# Schematic_DE1_Project_2021-05-03.net
KiCad netlist of a schematic drawn in Altium Designer
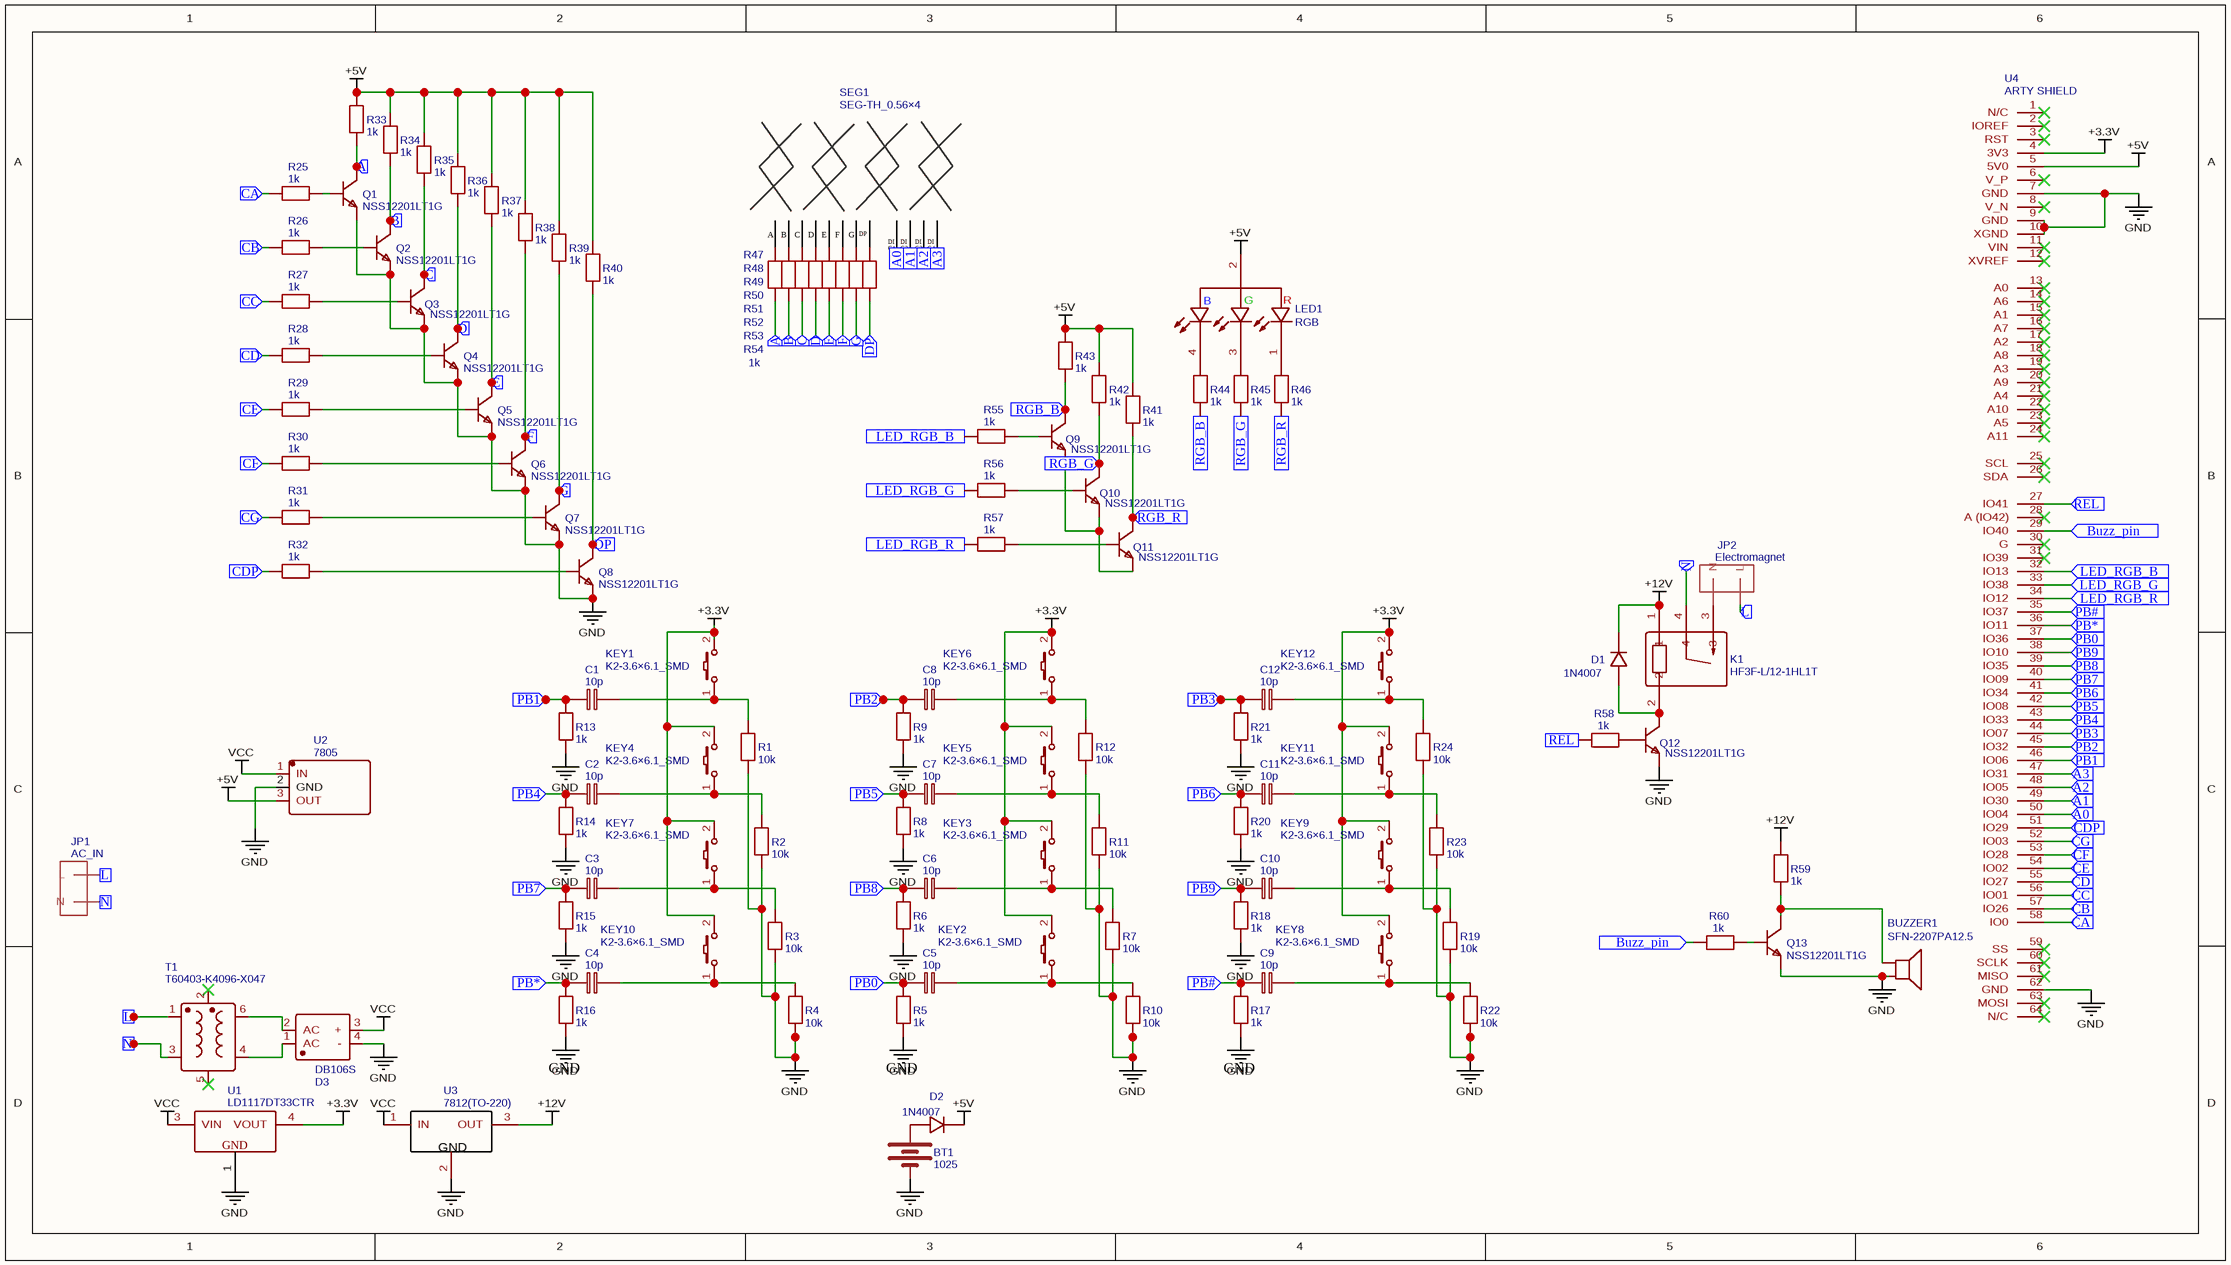
[diagram p0: Schematic_DE1_Project_2021-05-03.schdoc]

(export (version "E")
  (design (tool "Eeschema 10.0.6"))
  (components
    (comp (ref "BT1")
      (value "1025")
      (fields (field (name "BOM_SUPPLIER PART") "C238060") (field (name "CONTRIBUTOR") "LCSC"))
      (libsource (lib "altium-import") (part "root_3_1025_"))
    )
    (comp (ref "BUZZER1")
      (value "SFN-2207PA12.5")
      (fields (field (name "BOM_SUPPLIER PART") "C360602") (field (name "CONTRIBUTOR") "LCSC"))
      (libsource (lib "altium-import") (part "root_0_SFN-2207PA12.5_"))
    )
    (comp (ref "C1")
      (value "10p")
      (fields (field (name "CONTRIBUTOR") "LCEDA_Lib"))
      (libsource (lib "altium-import") (part "root_0_10p_"))
    )
    (comp (ref "C2")
      (value "10p")
      (fields (field (name "CONTRIBUTOR") "LCEDA_Lib"))
      (libsource (lib "altium-import") (part "root_0_10p_"))
    )
    (comp (ref "C3")
      (value "10p")
      (fields (field (name "CONTRIBUTOR") "LCEDA_Lib"))
      (libsource (lib "altium-import") (part "root_0_10p_"))
    )
    (comp (ref "C4")
      (value "10p")
      (fields (field (name "CONTRIBUTOR") "LCEDA_Lib"))
      (libsource (lib "altium-import") (part "root_0_10p_"))
    )
    (comp (ref "C5")
      (value "10p")
      (fields (field (name "CONTRIBUTOR") "LCEDA_Lib"))
      (libsource (lib "altium-import") (part "root_0_10p_"))
    )
    (comp (ref "C6")
      (value "10p")
      (fields (field (name "CONTRIBUTOR") "LCEDA_Lib"))
      (libsource (lib "altium-import") (part "root_0_10p_"))
    )
    (comp (ref "C7")
      (value "10p")
      (fields (field (name "CONTRIBUTOR") "LCEDA_Lib"))
      (libsource (lib "altium-import") (part "root_0_10p_"))
    )
    (comp (ref "C8")
      (value "10p")
      (fields (field (name "CONTRIBUTOR") "LCEDA_Lib"))
      (libsource (lib "altium-import") (part "root_0_10p_"))
    )
    (comp (ref "C9")
      (value "10p")
      (fields (field (name "CONTRIBUTOR") "LCEDA_Lib"))
      (libsource (lib "altium-import") (part "root_0_10p_"))
    )
    (comp (ref "C10")
      (value "10p")
      (fields (field (name "CONTRIBUTOR") "LCEDA_Lib"))
      (libsource (lib "altium-import") (part "root_0_10p_"))
    )
    (comp (ref "C11")
      (value "10p")
      (fields (field (name "CONTRIBUTOR") "LCEDA_Lib"))
      (libsource (lib "altium-import") (part "root_0_10p_"))
    )
    (comp (ref "C12")
      (value "10p")
      (fields (field (name "CONTRIBUTOR") "LCEDA_Lib"))
      (libsource (lib "altium-import") (part "root_0_10p_"))
    )
    (comp (ref "D1")
      (value "1N4007")
      (fields (field (name "BOM_SUPPLIER PART") "C106903") (field (name "CONTRIBUTOR") "LCEDA_Lib"))
      (libsource (lib "altium-import") (part "root_1_1N4007_"))
    )
    (comp (ref "D2")
      (value "1N4007")
      (fields (field (name "BOM_SUPPLIER PART") "C106903") (field (name "CONTRIBUTOR") "LCEDA_Lib"))
      (libsource (lib "altium-import") (part "root_0_1N4007_"))
    )
    (comp (ref "D3")
      (value "DB106S")
      (fields (field (name "BOM_SUPPLIER PART") "C139036") (field (name "CONTRIBUTOR") "LCSC"))
      (libsource (lib "altium-import") (part "root_0_DB106S_"))
    )
    (comp (ref "JP1")
      (value "AC_IN")
      (fields (field (name "CONTRIBUTOR") "tianfeng"))
      (libsource (lib "altium-import") (part "root_1_AC_IN_"))
    )
    (comp (ref "JP2")
      (value "Electromagnet")
      (fields (field (name "CONTRIBUTOR") "tianfeng"))
      (libsource (lib "altium-import") (part "root_0_Electromagnet_"))
    )
    (comp (ref "K1")
      (value "HF3F-L/12-1HL1T")
      (fields (field (name "BOM_SUPPLIER PART") "C190456") (field (name "CONTRIBUTOR") "LCSC"))
      (libsource (lib "altium-import") (part "root_0_HF3F-L/12-1HL1T_"))
    )
    (comp (ref "KEY1")
      (value "K2-3.6×6.1_SMD")
      (fields
        (field (name "BOM_SUPPLIER PART") "C118141")
        (field (name "BOM_MANUFACTURER PART") "K2-1107ST-A4SW-06")
        (field (name "CONTRIBUTOR") "LCEDA_Lib")
      )
      (libsource (lib "altium-import") (part "root_1_K2-3.6×6.1_SMD_"))
    )
    (comp (ref "KEY2")
      (value "K2-3.6×6.1_SMD")
      (fields
        (field (name "BOM_SUPPLIER PART") "C118141")
        (field (name "BOM_MANUFACTURER PART") "K2-1107ST-A4SW-06")
        (field (name "CONTRIBUTOR") "LCEDA_Lib")
      )
      (libsource (lib "altium-import") (part "root_1_K2-3.6×6.1_SMD_"))
    )
    (comp (ref "KEY3")
      (value "K2-3.6×6.1_SMD")
      (fields
        (field (name "BOM_SUPPLIER PART") "C118141")
        (field (name "BOM_MANUFACTURER PART") "K2-1107ST-A4SW-06")
        (field (name "CONTRIBUTOR") "LCEDA_Lib")
      )
      (libsource (lib "altium-import") (part "root_1_K2-3.6×6.1_SMD_"))
    )
    (comp (ref "KEY4")
      (value "K2-3.6×6.1_SMD")
      (fields
        (field (name "BOM_SUPPLIER PART") "C118141")
        (field (name "BOM_MANUFACTURER PART") "K2-1107ST-A4SW-06")
        (field (name "CONTRIBUTOR") "LCEDA_Lib")
      )
      (libsource (lib "altium-import") (part "root_1_K2-3.6×6.1_SMD_"))
    )
    (comp (ref "KEY5")
      (value "K2-3.6×6.1_SMD")
      (fields
        (field (name "BOM_SUPPLIER PART") "C118141")
        (field (name "BOM_MANUFACTURER PART") "K2-1107ST-A4SW-06")
        (field (name "CONTRIBUTOR") "LCEDA_Lib")
      )
      (libsource (lib "altium-import") (part "root_1_K2-3.6×6.1_SMD_"))
    )
    (comp (ref "KEY6")
      (value "K2-3.6×6.1_SMD")
      (fields
        (field (name "BOM_SUPPLIER PART") "C118141")
        (field (name "BOM_MANUFACTURER PART") "K2-1107ST-A4SW-06")
        (field (name "CONTRIBUTOR") "LCEDA_Lib")
      )
      (libsource (lib "altium-import") (part "root_1_K2-3.6×6.1_SMD_"))
    )
    (comp (ref "KEY7")
      (value "K2-3.6×6.1_SMD")
      (fields
        (field (name "BOM_SUPPLIER PART") "C118141")
        (field (name "BOM_MANUFACTURER PART") "K2-1107ST-A4SW-06")
        (field (name "CONTRIBUTOR") "LCEDA_Lib")
      )
      (libsource (lib "altium-import") (part "root_1_K2-3.6×6.1_SMD_"))
    )
    (comp (ref "KEY8")
      (value "K2-3.6×6.1_SMD")
      (fields
        (field (name "BOM_SUPPLIER PART") "C118141")
        (field (name "BOM_MANUFACTURER PART") "K2-1107ST-A4SW-06")
        (field (name "CONTRIBUTOR") "LCEDA_Lib")
      )
      (libsource (lib "altium-import") (part "root_1_K2-3.6×6.1_SMD_"))
    )
    (comp (ref "KEY9")
      (value "K2-3.6×6.1_SMD")
      (fields
        (field (name "BOM_SUPPLIER PART") "C118141")
        (field (name "BOM_MANUFACTURER PART") "K2-1107ST-A4SW-06")
        (field (name "CONTRIBUTOR") "LCEDA_Lib")
      )
      (libsource (lib "altium-import") (part "root_1_K2-3.6×6.1_SMD_"))
    )
    (comp (ref "KEY10")
      (value "K2-3.6×6.1_SMD")
      (fields
        (field (name "BOM_SUPPLIER PART") "C118141")
        (field (name "BOM_MANUFACTURER PART") "K2-1107ST-A4SW-06")
        (field (name "CONTRIBUTOR") "LCEDA_Lib")
      )
      (libsource (lib "altium-import") (part "root_1_K2-3.6×6.1_SMD_"))
    )
    (comp (ref "KEY11")
      (value "K2-3.6×6.1_SMD")
      (fields
        (field (name "BOM_SUPPLIER PART") "C118141")
        (field (name "BOM_MANUFACTURER PART") "K2-1107ST-A4SW-06")
        (field (name "CONTRIBUTOR") "LCEDA_Lib")
      )
      (libsource (lib "altium-import") (part "root_1_K2-3.6×6.1_SMD_"))
    )
    (comp (ref "KEY12")
      (value "K2-3.6×6.1_SMD")
      (fields
        (field (name "BOM_SUPPLIER PART") "C118141")
        (field (name "BOM_MANUFACTURER PART") "K2-1107ST-A4SW-06")
        (field (name "CONTRIBUTOR") "LCEDA_Lib")
      )
      (libsource (lib "altium-import") (part "root_1_K2-3.6×6.1_SMD_"))
    )
    (comp (ref "LED1")
      (value "RGB")
      (fields
        (field (name "BOM_MANUFACTURER PART") "φ5 RGB Transparent LED")
        (field (name "BOM_SUPPLIER PART") "C32985")
        (field (name "CONTRIBUTOR") "LCSC")
      )
      (libsource (lib "altium-import") (part "root_0_RGB_"))
    )
    (comp (ref "Q1")
      (value "NSS12201LT1G")
      (fields (field (name "BOM_SUPPLIER PART") "C242296") (field (name "CONTRIBUTOR") "LCSC"))
      (libsource (lib "altium-import") (part "root_0_NSS12201LT1G_"))
    )
    (comp (ref "Q2")
      (value "NSS12201LT1G")
      (fields (field (name "BOM_SUPPLIER PART") "C242296") (field (name "CONTRIBUTOR") "LCSC"))
      (libsource (lib "altium-import") (part "root_0_NSS12201LT1G_"))
    )
    (comp (ref "Q3")
      (value "NSS12201LT1G")
      (fields (field (name "BOM_SUPPLIER PART") "C242296") (field (name "CONTRIBUTOR") "LCSC"))
      (libsource (lib "altium-import") (part "root_0_NSS12201LT1G_"))
    )
    (comp (ref "Q4")
      (value "NSS12201LT1G")
      (fields (field (name "BOM_SUPPLIER PART") "C242296") (field (name "CONTRIBUTOR") "LCSC"))
      (libsource (lib "altium-import") (part "root_0_NSS12201LT1G_"))
    )
    (comp (ref "Q5")
      (value "NSS12201LT1G")
      (fields (field (name "BOM_SUPPLIER PART") "C242296") (field (name "CONTRIBUTOR") "LCSC"))
      (libsource (lib "altium-import") (part "root_0_NSS12201LT1G_"))
    )
    (comp (ref "Q6")
      (value "NSS12201LT1G")
      (fields (field (name "BOM_SUPPLIER PART") "C242296") (field (name "CONTRIBUTOR") "LCSC"))
      (libsource (lib "altium-import") (part "root_0_NSS12201LT1G_"))
    )
    (comp (ref "Q7")
      (value "NSS12201LT1G")
      (fields (field (name "BOM_SUPPLIER PART") "C242296") (field (name "CONTRIBUTOR") "LCSC"))
      (libsource (lib "altium-import") (part "root_0_NSS12201LT1G_"))
    )
    (comp (ref "Q8")
      (value "NSS12201LT1G")
      (fields (field (name "BOM_SUPPLIER PART") "C242296") (field (name "CONTRIBUTOR") "LCSC"))
      (libsource (lib "altium-import") (part "root_0_NSS12201LT1G_"))
    )
    (comp (ref "Q9")
      (value "NSS12201LT1G")
      (fields (field (name "BOM_SUPPLIER PART") "C242296") (field (name "CONTRIBUTOR") "LCSC"))
      (libsource (lib "altium-import") (part "root_0_NSS12201LT1G_"))
    )
    (comp (ref "Q10")
      (value "NSS12201LT1G")
      (fields (field (name "BOM_SUPPLIER PART") "C242296") (field (name "CONTRIBUTOR") "LCSC"))
      (libsource (lib "altium-import") (part "root_0_NSS12201LT1G_"))
    )
    (comp (ref "Q11")
      (value "NSS12201LT1G")
      (fields (field (name "BOM_SUPPLIER PART") "C242296") (field (name "CONTRIBUTOR") "LCSC"))
      (libsource (lib "altium-import") (part "root_0_NSS12201LT1G_"))
    )
    (comp (ref "Q12")
      (value "NSS12201LT1G")
      (fields (field (name "BOM_SUPPLIER PART") "C242296") (field (name "CONTRIBUTOR") "LCSC"))
      (libsource (lib "altium-import") (part "root_0_NSS12201LT1G_"))
    )
    (comp (ref "Q13")
      (value "NSS12201LT1G")
      (fields (field (name "BOM_SUPPLIER PART") "C242296") (field (name "CONTRIBUTOR") "LCSC"))
      (libsource (lib "altium-import") (part "root_0_NSS12201LT1G_"))
    )
    (comp (ref "R1")
      (value "10k")
      (fields (field (name "CONTRIBUTOR") "LCEDA_Lib"))
      (libsource (lib "altium-import") (part "root_1_10k_"))
    )
    (comp (ref "R2")
      (value "10k")
      (fields (field (name "CONTRIBUTOR") "LCEDA_Lib"))
      (libsource (lib "altium-import") (part "root_1_10k_"))
    )
    (comp (ref "R3")
      (value "10k")
      (fields (field (name "CONTRIBUTOR") "LCEDA_Lib"))
      (libsource (lib "altium-import") (part "root_1_10k_"))
    )
    (comp (ref "R4")
      (value "10k")
      (fields (field (name "CONTRIBUTOR") "LCEDA_Lib"))
      (libsource (lib "altium-import") (part "root_1_10k_"))
    )
    (comp (ref "R5")
      (value "1k")
      (fields (field (name "CONTRIBUTOR") "LCEDA_Lib"))
      (libsource (lib "altium-import") (part "root_1_1k_"))
    )
    (comp (ref "R6")
      (value "1k")
      (fields (field (name "CONTRIBUTOR") "LCEDA_Lib"))
      (libsource (lib "altium-import") (part "root_1_1k_"))
    )
    (comp (ref "R7")
      (value "10k")
      (fields (field (name "CONTRIBUTOR") "LCEDA_Lib"))
      (libsource (lib "altium-import") (part "root_1_10k_"))
    )
    (comp (ref "R8")
      (value "1k")
      (fields (field (name "CONTRIBUTOR") "LCEDA_Lib"))
      (libsource (lib "altium-import") (part "root_1_1k_"))
    )
    (comp (ref "R9")
      (value "1k")
      (fields (field (name "CONTRIBUTOR") "LCEDA_Lib"))
      (libsource (lib "altium-import") (part "root_1_1k_"))
    )
    (comp (ref "R10")
      (value "10k")
      (fields (field (name "CONTRIBUTOR") "LCEDA_Lib"))
      (libsource (lib "altium-import") (part "root_1_10k_"))
    )
    (comp (ref "R11")
      (value "10k")
      (fields (field (name "CONTRIBUTOR") "LCEDA_Lib"))
      (libsource (lib "altium-import") (part "root_1_10k_"))
    )
    (comp (ref "R12")
      (value "10k")
      (fields (field (name "CONTRIBUTOR") "LCEDA_Lib"))
      (libsource (lib "altium-import") (part "root_1_10k_"))
    )
    (comp (ref "R13")
      (value "1k")
      (fields (field (name "CONTRIBUTOR") "LCEDA_Lib"))
      (libsource (lib "altium-import") (part "root_1_1k_"))
    )
    (comp (ref "R14")
      (value "1k")
      (fields (field (name "CONTRIBUTOR") "LCEDA_Lib"))
      (libsource (lib "altium-import") (part "root_1_1k_"))
    )
    (comp (ref "R15")
      (value "1k")
      (fields (field (name "CONTRIBUTOR") "LCEDA_Lib"))
      (libsource (lib "altium-import") (part "root_1_1k_"))
    )
    (comp (ref "R16")
      (value "1k")
      (fields (field (name "CONTRIBUTOR") "LCEDA_Lib"))
      (libsource (lib "altium-import") (part "root_1_1k_"))
    )
    (comp (ref "R17")
      (value "1k")
      (fields (field (name "CONTRIBUTOR") "LCEDA_Lib"))
      (libsource (lib "altium-import") (part "root_1_1k_"))
    )
    (comp (ref "R18")
      (value "1k")
      (fields (field (name "CONTRIBUTOR") "LCEDA_Lib"))
      (libsource (lib "altium-import") (part "root_1_1k_"))
    )
    (comp (ref "R19")
      (value "10k")
      (fields (field (name "CONTRIBUTOR") "LCEDA_Lib"))
      (libsource (lib "altium-import") (part "root_1_10k_"))
    )
    (comp (ref "R20")
      (value "1k")
      (fields (field (name "CONTRIBUTOR") "LCEDA_Lib"))
      (libsource (lib "altium-import") (part "root_1_1k_"))
    )
    (comp (ref "R21")
      (value "1k")
      (fields (field (name "CONTRIBUTOR") "LCEDA_Lib"))
      (libsource (lib "altium-import") (part "root_1_1k_"))
    )
    (comp (ref "R22")
      (value "10k")
      (fields (field (name "CONTRIBUTOR") "LCEDA_Lib"))
      (libsource (lib "altium-import") (part "root_1_10k_"))
    )
    (comp (ref "R23")
      (value "10k")
      (fields (field (name "CONTRIBUTOR") "LCEDA_Lib"))
      (libsource (lib "altium-import") (part "root_1_10k_"))
    )
    (comp (ref "R24")
      (value "10k")
      (fields (field (name "CONTRIBUTOR") "LCEDA_Lib"))
      (libsource (lib "altium-import") (part "root_1_10k_"))
    )
    (comp (ref "R25")
      (value "1k")
      (fields (field (name "CONTRIBUTOR") "LCEDA_Lib"))
      (libsource (lib "altium-import") (part "root_0_1k_"))
    )
    (comp (ref "R26")
      (value "1k")
      (fields (field (name "CONTRIBUTOR") "LCEDA_Lib"))
      (libsource (lib "altium-import") (part "root_0_1k_"))
    )
    (comp (ref "R27")
      (value "1k")
      (fields (field (name "CONTRIBUTOR") "LCEDA_Lib"))
      (libsource (lib "altium-import") (part "root_0_1k_"))
    )
    (comp (ref "R28")
      (value "1k")
      (fields (field (name "CONTRIBUTOR") "LCEDA_Lib"))
      (libsource (lib "altium-import") (part "root_0_1k_"))
    )
    (comp (ref "R29")
      (value "1k")
      (fields (field (name "CONTRIBUTOR") "LCEDA_Lib"))
      (libsource (lib "altium-import") (part "root_0_1k_"))
    )
    (comp (ref "R30")
      (value "1k")
      (fields (field (name "CONTRIBUTOR") "LCEDA_Lib"))
      (libsource (lib "altium-import") (part "root_0_1k_"))
    )
    (comp (ref "R31")
      (value "1k")
      (fields (field (name "CONTRIBUTOR") "LCEDA_Lib"))
      (libsource (lib "altium-import") (part "root_0_1k_"))
    )
    (comp (ref "R32")
      (value "1k")
      (fields (field (name "CONTRIBUTOR") "LCEDA_Lib"))
      (libsource (lib "altium-import") (part "root_0_1k_"))
    )
    (comp (ref "R33")
      (value "1k")
      (fields (field (name "CONTRIBUTOR") "LCEDA_Lib"))
      (libsource (lib "altium-import") (part "root_1_1k_"))
    )
    (comp (ref "R34")
      (value "1k")
      (fields (field (name "CONTRIBUTOR") "LCEDA_Lib"))
      (libsource (lib "altium-import") (part "root_1_1k_"))
    )
    (comp (ref "R35")
      (value "1k")
      (fields (field (name "CONTRIBUTOR") "LCEDA_Lib"))
      (libsource (lib "altium-import") (part "root_1_1k_"))
    )
    (comp (ref "R36")
      (value "1k")
      (fields (field (name "CONTRIBUTOR") "LCEDA_Lib"))
      (libsource (lib "altium-import") (part "root_1_1k_"))
    )
    (comp (ref "R37")
      (value "1k")
      (fields (field (name "CONTRIBUTOR") "LCEDA_Lib"))
      (libsource (lib "altium-import") (part "root_1_1k_"))
    )
    (comp (ref "R38")
      (value "1k")
      (fields (field (name "CONTRIBUTOR") "LCEDA_Lib"))
      (libsource (lib "altium-import") (part "root_1_1k_"))
    )
    (comp (ref "R39")
      (value "1k")
      (fields (field (name "CONTRIBUTOR") "LCEDA_Lib"))
      (libsource (lib "altium-import") (part "root_1_1k_"))
    )
    (comp (ref "R40")
      (value "1k")
      (fields (field (name "CONTRIBUTOR") "LCEDA_Lib"))
      (libsource (lib "altium-import") (part "root_1_1k_"))
    )
    (comp (ref "R41")
      (value "1k")
      (fields (field (name "CONTRIBUTOR") "LCEDA_Lib"))
      (libsource (lib "altium-import") (part "root_1_1k_"))
    )
    (comp (ref "R42")
      (value "1k")
      (fields (field (name "CONTRIBUTOR") "LCEDA_Lib"))
      (libsource (lib "altium-import") (part "root_1_1k_"))
    )
    (comp (ref "R43")
      (value "1k")
      (fields (field (name "CONTRIBUTOR") "LCEDA_Lib"))
      (libsource (lib "altium-import") (part "root_1_1k_"))
    )
    (comp (ref "R44")
      (value "1k")
      (fields (field (name "CONTRIBUTOR") "LCEDA_Lib"))
      (libsource (lib "altium-import") (part "root_1_1k_"))
    )
    (comp (ref "R45")
      (value "1k")
      (fields (field (name "CONTRIBUTOR") "LCEDA_Lib"))
      (libsource (lib "altium-import") (part "root_1_1k_"))
    )
    (comp (ref "R46")
      (value "1k")
      (fields (field (name "CONTRIBUTOR") "LCEDA_Lib"))
      (libsource (lib "altium-import") (part "root_1_1k_"))
    )
    (comp (ref "R47")
      (value "1k")
      (fields (field (name "CONTRIBUTOR") "LCEDA_Lib"))
      (libsource (lib "altium-import") (part "root_1_1k_"))
    )
    (comp (ref "R48")
      (value "1k")
      (fields (field (name "CONTRIBUTOR") "LCEDA_Lib"))
      (libsource (lib "altium-import") (part "root_1_1k_"))
    )
    (comp (ref "R49")
      (value "1k")
      (fields (field (name "CONTRIBUTOR") "LCEDA_Lib"))
      (libsource (lib "altium-import") (part "root_1_1k_"))
    )
    (comp (ref "R50")
      (value "1k")
      (fields (field (name "CONTRIBUTOR") "LCEDA_Lib"))
      (libsource (lib "altium-import") (part "root_1_1k_"))
    )
    (comp (ref "R51")
      (value "1k")
      (fields (field (name "CONTRIBUTOR") "LCEDA_Lib"))
      (libsource (lib "altium-import") (part "root_1_1k_"))
    )
    (comp (ref "R52")
      (value "1k")
      (fields (field (name "CONTRIBUTOR") "LCEDA_Lib"))
      (libsource (lib "altium-import") (part "root_1_1k_"))
    )
    (comp (ref "R53")
      (value "1k")
      (fields (field (name "CONTRIBUTOR") "LCEDA_Lib"))
      (libsource (lib "altium-import") (part "root_1_1k_"))
    )
    (comp (ref "R54")
      (value "1k")
      (fields (field (name "CONTRIBUTOR") "LCEDA_Lib"))
      (libsource (lib "altium-import") (part "root_1_1k_"))
    )
    (comp (ref "R55")
      (value "1k")
      (fields (field (name "CONTRIBUTOR") "LCEDA_Lib"))
      (libsource (lib "altium-import") (part "root_0_1k_"))
    )
    (comp (ref "R56")
      (value "1k")
      (fields (field (name "CONTRIBUTOR") "LCEDA_Lib"))
      (libsource (lib "altium-import") (part "root_0_1k_"))
    )
    (comp (ref "R57")
      (value "1k")
      (fields (field (name "CONTRIBUTOR") "LCEDA_Lib"))
      (libsource (lib "altium-import") (part "root_0_1k_"))
    )
    (comp (ref "R58")
      (value "1k")
      (fields (field (name "CONTRIBUTOR") "LCEDA_Lib"))
      (libsource (lib "altium-import") (part "root_0_1k_"))
    )
    (comp (ref "R59")
      (value "1k")
      (fields (field (name "CONTRIBUTOR") "LCEDA_Lib"))
      (libsource (lib "altium-import") (part "root_1_1k_"))
    )
    (comp (ref "R60")
      (value "1k")
      (fields (field (name "CONTRIBUTOR") "LCEDA_Lib"))
      (libsource (lib "altium-import") (part "root_0_1k_"))
    )
    (comp (ref "SEG1")
      (value "SEG-TH_0.56×4")
      (fields (field (name "BOM_SUPPLIER PART") "C109200") (field (name "CONTRIBUTOR") "LCEDA_01"))
      (libsource (lib "altium-import") (part "root_0_SEG-TH_0.56×4_"))
    )
    (comp (ref "T1")
      (value "T60403-K4096-X047")
      (fields (field (name "BOM_SUPPLIER PART") "C465442") (field (name "CONTRIBUTOR") "LCSC"))
      (libsource (lib "altium-import") (part "root_0_T60403-K4096-X047_"))
    )
    (comp (ref "U1")
      (value "LD1117DT33CTR")
      (fields (field (name "BOM_SUPPLIER PART") "C36395"))
      (libsource (lib "altium-import") (part "root_0_LD1117DT33CTR_"))
    )
    (comp (ref "U2")
      (value "7805")
      (fields (field (name "BOM_SUPPLIER PART") "C305416") (field (name "CONTRIBUTOR") "LCSC"))
      (libsource (lib "altium-import") (part "root_0_7805_"))
    )
    (comp (ref "U3")
      (value "7812(TO-220)")
      (fields
        (field (name "BOM_MANUFACTURER PART") "MC7812BTG")
        (field (name "BOM_SUPPLIER PART") "C45387")
        (field (name "CONTRIBUTOR") "LCEDA_Lib")
      )
      (libsource (lib "altium-import") (part "root_0_7812(TO-220)_"))
    )
    (comp (ref "U4")
      (value "ARTY SHIELD")
      (fields
        (field (name "BOM_MANUFACTURER PART") "MPT-DTI-UAV-00000")
        (field (name "CONTRIBUTOR") "Scott Ramirez")
      )
      (libsource (lib "altium-import") (part "root_0_ARTY SHIELD_"))
    )
  )
  (nets
    (net (code "1") (name "+3.3V") (class "Default")
      (node (ref "KEY1") (pin "2") (pinfunction "2_2") (pintype "passive"))
      (node (ref "KEY10") (pin "2") (pinfunction "2_2") (pintype "passive"))
      (node (ref "KEY11") (pin "2") (pinfunction "2_2") (pintype "passive"))
      (node (ref "KEY12") (pin "2") (pinfunction "2_2") (pintype "passive"))
      (node (ref "KEY2") (pin "2") (pinfunction "2_2") (pintype "passive"))
      (node (ref "KEY3") (pin "2") (pinfunction "2_2") (pintype "passive"))
      (node (ref "KEY4") (pin "2") (pinfunction "2_2") (pintype "passive"))
      (node (ref "KEY5") (pin "2") (pinfunction "2_2") (pintype "passive"))
      (node (ref "KEY6") (pin "2") (pinfunction "2_2") (pintype "passive"))
      (node (ref "KEY7") (pin "2") (pinfunction "2_2") (pintype "passive"))
      (node (ref "KEY8") (pin "2") (pinfunction "2_2") (pintype "passive"))
      (node (ref "KEY9") (pin "2") (pinfunction "2_2") (pintype "passive"))
      (node (ref "U1") (pin "4") (pinfunction "VOUT_4") (pintype "passive"))
      (node (ref "U4") (pin "4") (pinfunction "3V3_4") (pintype "passive"))
    )
    (net (code "2") (name "+5V") (class "Default")
      (node (ref "D2") (pin "1") (pinfunction "1_1") (pintype "passive"))
      (node (ref "LED1") (pin "2") (pinfunction "CA_2") (pintype "passive"))
      (node (ref "R33") (pin "2") (pinfunction "2_2") (pintype "passive"))
      (node (ref "R34") (pin "2") (pinfunction "2_2") (pintype "passive"))
      (node (ref "R35") (pin "2") (pinfunction "2_2") (pintype "passive"))
      (node (ref "R36") (pin "2") (pinfunction "2_2") (pintype "passive"))
      (node (ref "R37") (pin "2") (pinfunction "2_2") (pintype "passive"))
      (node (ref "R38") (pin "2") (pinfunction "2_2") (pintype "passive"))
      (node (ref "R39") (pin "2") (pinfunction "2_2") (pintype "passive"))
      (node (ref "R40") (pin "2") (pinfunction "2_2") (pintype "passive"))
      (node (ref "R41") (pin "2") (pinfunction "2_2") (pintype "passive"))
      (node (ref "R42") (pin "2") (pinfunction "2_2") (pintype "passive"))
      (node (ref "R43") (pin "2") (pinfunction "2_2") (pintype "passive"))
      (node (ref "U2") (pin "3") (pinfunction "OUT_3") (pintype "passive"))
      (node (ref "U4") (pin "5") (pinfunction "5V0_5") (pintype "passive"))
    )
    (net (code "3") (name "+12V") (class "Default")
      (node (ref "D1") (pin "1") (pinfunction "1_1") (pintype "passive"))
      (node (ref "K1") (pin "1") (pinfunction "1_1") (pintype "passive"))
      (node (ref "R59") (pin "2") (pinfunction "2_2") (pintype "passive"))
      (node (ref "U3") (pin "3") (pinfunction "OUT_3") (pintype "passive"))
    )
    (net (code "4") (name "/A") (class "Default")
      (node (ref "Q1") (pin "3") (pinfunction "C_3") (pintype "passive"))
      (node (ref "R33") (pin "1") (pinfunction "1_1") (pintype "passive"))
      (node (ref "R47") (pin "1") (pinfunction "1_1") (pintype "passive"))
    )
    (net (code "5") (name "/A0") (class "Default")
      (node (ref "SEG1") (pin "12") (pinfunction "DIG1_12") (pintype "passive"))
      (node (ref "U4") (pin "50") (pinfunction "IO04_50") (pintype "passive"))
    )
    (net (code "6") (name "/A1") (class "Default")
      (node (ref "SEG1") (pin "9") (pinfunction "DIG2_9") (pintype "passive"))
      (node (ref "U4") (pin "49") (pinfunction "IO30_49") (pintype "passive"))
    )
    (net (code "7") (name "/A2") (class "Default")
      (node (ref "SEG1") (pin "8") (pinfunction "DIG3_8") (pintype "passive"))
      (node (ref "U4") (pin "48") (pinfunction "IO05_48") (pintype "passive"))
    )
    (net (code "8") (name "/A3") (class "Default")
      (node (ref "SEG1") (pin "6") (pinfunction "DIG4_6") (pintype "passive"))
      (node (ref "U4") (pin "47") (pinfunction "IO31_47") (pintype "passive"))
    )
    (net (code "9") (name "/B") (class "Default")
      (node (ref "Q2") (pin "3") (pinfunction "C_3") (pintype "passive"))
      (node (ref "R34") (pin "1") (pinfunction "1_1") (pintype "passive"))
      (node (ref "R48") (pin "1") (pinfunction "1_1") (pintype "passive"))
    )
    (net (code "10") (name "/Buzz_pin") (class "Default")
      (node (ref "R60") (pin "1") (pinfunction "1_1") (pintype "passive"))
      (node (ref "U4") (pin "29") (pinfunction "IO40_29") (pintype "passive"))
    )
    (net (code "11") (name "/C") (class "Default")
      (node (ref "Q3") (pin "3") (pinfunction "C_3") (pintype "passive"))
      (node (ref "R35") (pin "1") (pinfunction "1_1") (pintype "passive"))
      (node (ref "R49") (pin "1") (pinfunction "1_1") (pintype "passive"))
    )
    (net (code "12") (name "/CA") (class "Default")
      (node (ref "R25") (pin "1") (pinfunction "1_1") (pintype "passive"))
      (node (ref "U4") (pin "58") (pinfunction "IO0_58") (pintype "passive"))
    )
    (net (code "13") (name "/CB") (class "Default")
      (node (ref "R26") (pin "1") (pinfunction "1_1") (pintype "passive"))
      (node (ref "U4") (pin "57") (pinfunction "IO26_57") (pintype "passive"))
    )
    (net (code "14") (name "/CC") (class "Default")
      (node (ref "R27") (pin "1") (pinfunction "1_1") (pintype "passive"))
      (node (ref "U4") (pin "56") (pinfunction "IO01_56") (pintype "passive"))
    )
    (net (code "15") (name "/CD") (class "Default")
      (node (ref "R28") (pin "1") (pinfunction "1_1") (pintype "passive"))
      (node (ref "U4") (pin "55") (pinfunction "IO27_55") (pintype "passive"))
    )
    (net (code "16") (name "/CDP") (class "Default")
      (node (ref "R32") (pin "1") (pinfunction "1_1") (pintype "passive"))
      (node (ref "U4") (pin "51") (pinfunction "IO29_51") (pintype "passive"))
    )
    (net (code "17") (name "/CE") (class "Default")
      (node (ref "R29") (pin "1") (pinfunction "1_1") (pintype "passive"))
      (node (ref "U4") (pin "54") (pinfunction "IO02_54") (pintype "passive"))
    )
    (net (code "18") (name "/CF") (class "Default")
      (node (ref "R30") (pin "1") (pinfunction "1_1") (pintype "passive"))
      (node (ref "U4") (pin "53") (pinfunction "IO28_53") (pintype "passive"))
    )
    (net (code "19") (name "/CG") (class "Default")
      (node (ref "R31") (pin "1") (pinfunction "1_1") (pintype "passive"))
      (node (ref "U4") (pin "52") (pinfunction "IO03_52") (pintype "passive"))
    )
    (net (code "20") (name "/D") (class "Default")
      (node (ref "Q4") (pin "3") (pinfunction "C_3") (pintype "passive"))
      (node (ref "R36") (pin "1") (pinfunction "1_1") (pintype "passive"))
      (node (ref "R50") (pin "1") (pinfunction "1_1") (pintype "passive"))
    )
    (net (code "21") (name "/DP") (class "Default")
      (node (ref "Q8") (pin "3") (pinfunction "C_3") (pintype "passive"))
      (node (ref "R40") (pin "1") (pinfunction "1_1") (pintype "passive"))
      (node (ref "R54") (pin "1") (pinfunction "1_1") (pintype "passive"))
    )
    (net (code "22") (name "/E") (class "Default")
      (node (ref "Q5") (pin "3") (pinfunction "C_3") (pintype "passive"))
      (node (ref "R37") (pin "1") (pinfunction "1_1") (pintype "passive"))
      (node (ref "R51") (pin "1") (pinfunction "1_1") (pintype "passive"))
    )
    (net (code "23") (name "/F") (class "Default")
      (node (ref "Q6") (pin "3") (pinfunction "C_3") (pintype "passive"))
      (node (ref "R38") (pin "1") (pinfunction "1_1") (pintype "passive"))
      (node (ref "R52") (pin "1") (pinfunction "1_1") (pintype "passive"))
    )
    (net (code "24") (name "/G") (class "Default")
      (node (ref "Q7") (pin "3") (pinfunction "C_3") (pintype "passive"))
      (node (ref "R39") (pin "1") (pinfunction "1_1") (pintype "passive"))
      (node (ref "R53") (pin "1") (pinfunction "1_1") (pintype "passive"))
    )
    (net (code "25") (name "/L") (class "Default")
      (node (ref "JP1") (pin "VCC") (pinfunction "L_VCC") (pintype "passive"))
      (node (ref "JP2") (pin "VCC") (pinfunction "L_VCC") (pintype "passive"))
      (node (ref "T1") (pin "1") (pinfunction "1_1") (pintype "passive"))
    )
    (net (code "26") (name "/LED_RGB_B") (class "Default")
      (node (ref "R55") (pin "1") (pinfunction "1_1") (pintype "passive"))
      (node (ref "U4") (pin "32") (pinfunction "IO13_32") (pintype "passive"))
    )
    (net (code "27") (name "/LED_RGB_G") (class "Default")
      (node (ref "R56") (pin "1") (pinfunction "1_1") (pintype "passive"))
      (node (ref "U4") (pin "33") (pinfunction "IO38_33") (pintype "passive"))
    )
    (net (code "28") (name "/LED_RGB_R") (class "Default")
      (node (ref "R57") (pin "1") (pinfunction "1_1") (pintype "passive"))
      (node (ref "U4") (pin "34") (pinfunction "IO12_34") (pintype "passive"))
    )
    (net (code "29") (name "/N") (class "Default")
      (node (ref "JP1") (pin "12VIN") (pinfunction "N_12VIN") (pintype "passive"))
      (node (ref "K1") (pin "4") (pinfunction "4_4") (pintype "passive"))
      (node (ref "T1") (pin "3") (pinfunction "3_3") (pintype "passive"))
    )
    (net (code "30") (name "/PB#") (class "Default")
      (node (ref "C9") (pin "1") (pinfunction "1_1") (pintype "passive"))
      (node (ref "R17") (pin "2") (pinfunction "2_2") (pintype "passive"))
      (node (ref "U4") (pin "35") (pinfunction "IO37_35") (pintype "passive"))
    )
    (net (code "31") (name "/PB*") (class "Default")
      (node (ref "C4") (pin "1") (pinfunction "1_1") (pintype "passive"))
      (node (ref "R16") (pin "2") (pinfunction "2_2") (pintype "passive"))
      (node (ref "U4") (pin "36") (pinfunction "IO11_36") (pintype "passive"))
    )
    (net (code "32") (name "/PB0") (class "Default")
      (node (ref "C5") (pin "1") (pinfunction "1_1") (pintype "passive"))
      (node (ref "R5") (pin "2") (pinfunction "2_2") (pintype "passive"))
      (node (ref "U4") (pin "37") (pinfunction "IO36_37") (pintype "passive"))
    )
    (net (code "33") (name "/PB1") (class "Default")
      (node (ref "C1") (pin "1") (pinfunction "1_1") (pintype "passive"))
      (node (ref "R13") (pin "2") (pinfunction "2_2") (pintype "passive"))
      (node (ref "U4") (pin "46") (pinfunction "IO06_46") (pintype "passive"))
    )
    (net (code "34") (name "/PB2") (class "Default")
      (node (ref "C8") (pin "1") (pinfunction "1_1") (pintype "passive"))
      (node (ref "R9") (pin "2") (pinfunction "2_2") (pintype "passive"))
      (node (ref "U4") (pin "45") (pinfunction "IO32_45") (pintype "passive"))
    )
    (net (code "35") (name "/PB3") (class "Default")
      (node (ref "C12") (pin "1") (pinfunction "1_1") (pintype "passive"))
      (node (ref "R21") (pin "2") (pinfunction "2_2") (pintype "passive"))
      (node (ref "U4") (pin "44") (pinfunction "IO07_44") (pintype "passive"))
    )
    (net (code "36") (name "/PB4") (class "Default")
      (node (ref "C2") (pin "1") (pinfunction "1_1") (pintype "passive"))
      (node (ref "R14") (pin "2") (pinfunction "2_2") (pintype "passive"))
      (node (ref "U4") (pin "43") (pinfunction "IO33_43") (pintype "passive"))
    )
    (net (code "37") (name "/PB5") (class "Default")
      (node (ref "C7") (pin "1") (pinfunction "1_1") (pintype "passive"))
      (node (ref "R8") (pin "2") (pinfunction "2_2") (pintype "passive"))
      (node (ref "U4") (pin "42") (pinfunction "IO08_42") (pintype "passive"))
    )
    (net (code "38") (name "/PB6") (class "Default")
      (node (ref "C11") (pin "1") (pinfunction "1_1") (pintype "passive"))
      (node (ref "R20") (pin "2") (pinfunction "2_2") (pintype "passive"))
      (node (ref "U4") (pin "41") (pinfunction "IO34_41") (pintype "passive"))
    )
    (net (code "39") (name "/PB7") (class "Default")
      (node (ref "C3") (pin "1") (pinfunction "1_1") (pintype "passive"))
      (node (ref "R15") (pin "2") (pinfunction "2_2") (pintype "passive"))
      (node (ref "U4") (pin "40") (pinfunction "IO09_40") (pintype "passive"))
    )
    (net (code "40") (name "/PB8") (class "Default")
      (node (ref "C6") (pin "1") (pinfunction "1_1") (pintype "passive"))
      (node (ref "R6") (pin "2") (pinfunction "2_2") (pintype "passive"))
      (node (ref "U4") (pin "39") (pinfunction "IO35_39") (pintype "passive"))
    )
    (net (code "41") (name "/PB9") (class "Default")
      (node (ref "C10") (pin "1") (pinfunction "1_1") (pintype "passive"))
      (node (ref "R18") (pin "2") (pinfunction "2_2") (pintype "passive"))
      (node (ref "U4") (pin "38") (pinfunction "IO10_38") (pintype "passive"))
    )
    (net (code "42") (name "/REL") (class "Default")
      (node (ref "R58") (pin "1") (pinfunction "1_1") (pintype "passive"))
      (node (ref "U4") (pin "27") (pinfunction "IO41_27") (pintype "passive"))
    )
    (net (code "43") (name "/RGB_B") (class "Default")
      (node (ref "Q9") (pin "3") (pinfunction "C_3") (pintype "passive"))
      (node (ref "R43") (pin "1") (pinfunction "1_1") (pintype "passive"))
      (node (ref "R44") (pin "1") (pinfunction "1_1") (pintype "passive"))
    )
    (net (code "44") (name "/RGB_G") (class "Default")
      (node (ref "Q10") (pin "3") (pinfunction "C_3") (pintype "passive"))
      (node (ref "R42") (pin "1") (pinfunction "1_1") (pintype "passive"))
      (node (ref "R45") (pin "1") (pinfunction "1_1") (pintype "passive"))
    )
    (net (code "45") (name "/RGB_R") (class "Default")
      (node (ref "Q11") (pin "3") (pinfunction "C_3") (pintype "passive"))
      (node (ref "R41") (pin "1") (pinfunction "1_1") (pintype "passive"))
      (node (ref "R46") (pin "1") (pinfunction "1_1") (pintype "passive"))
    )
    (net (code "46") (name "GND") (class "Default")
      (node (ref "BT1") (pin "2") (pinfunction "-_2") (pintype "passive"))
      (node (ref "BUZZER1") (pin "2") (pinfunction "2_2") (pintype "passive"))
      (node (ref "D3") (pin "4") (pinfunction "-_4") (pintype "passive"))
      (node (ref "Q1") (pin "2") (pinfunction "E_2") (pintype "passive"))
      (node (ref "Q12") (pin "2") (pinfunction "E_2") (pintype "passive"))
      (node (ref "Q13") (pin "2") (pinfunction "E_2") (pintype "passive"))
      (node (ref "Q2") (pin "2") (pinfunction "E_2") (pintype "passive"))
      (node (ref "Q3") (pin "2") (pinfunction "E_2") (pintype "passive"))
      (node (ref "Q4") (pin "2") (pinfunction "E_2") (pintype "passive"))
      (node (ref "Q5") (pin "2") (pinfunction "E_2") (pintype "passive"))
      (node (ref "Q6") (pin "2") (pinfunction "E_2") (pintype "passive"))
      (node (ref "Q7") (pin "2") (pinfunction "E_2") (pintype "passive"))
      (node (ref "Q8") (pin "2") (pinfunction "E_2") (pintype "passive"))
      (node (ref "R1") (pin "1") (pinfunction "1_1") (pintype "passive"))
      (node (ref "R10") (pin "1") (pinfunction "1_1") (pintype "passive"))
      (node (ref "R11") (pin "1") (pinfunction "1_1") (pintype "passive"))
      (node (ref "R12") (pin "1") (pinfunction "1_1") (pintype "passive"))
      (node (ref "R13") (pin "1") (pinfunction "1_1") (pintype "passive"))
      (node (ref "R14") (pin "1") (pinfunction "1_1") (pintype "passive"))
      (node (ref "R15") (pin "1") (pinfunction "1_1") (pintype "passive"))
      (node (ref "R16") (pin "1") (pinfunction "1_1") (pintype "passive"))
      (node (ref "R17") (pin "1") (pinfunction "1_1") (pintype "passive"))
      (node (ref "R18") (pin "1") (pinfunction "1_1") (pintype "passive"))
      (node (ref "R19") (pin "1") (pinfunction "1_1") (pintype "passive"))
      (node (ref "R2") (pin "1") (pinfunction "1_1") (pintype "passive"))
      (node (ref "R20") (pin "1") (pinfunction "1_1") (pintype "passive"))
      (node (ref "R21") (pin "1") (pinfunction "1_1") (pintype "passive"))
      (node (ref "R22") (pin "1") (pinfunction "1_1") (pintype "passive"))
      (node (ref "R23") (pin "1") (pinfunction "1_1") (pintype "passive"))
      (node (ref "R24") (pin "1") (pinfunction "1_1") (pintype "passive"))
      (node (ref "R3") (pin "1") (pinfunction "1_1") (pintype "passive"))
      (node (ref "R4") (pin "1") (pinfunction "1_1") (pintype "passive"))
      (node (ref "R5") (pin "1") (pinfunction "1_1") (pintype "passive"))
      (node (ref "R6") (pin "1") (pinfunction "1_1") (pintype "passive"))
      (node (ref "R7") (pin "1") (pinfunction "1_1") (pintype "passive"))
      (node (ref "R8") (pin "1") (pinfunction "1_1") (pintype "passive"))
      (node (ref "R9") (pin "1") (pinfunction "1_1") (pintype "passive"))
      (node (ref "U1") (pin "1") (pinfunction "GND_1") (pintype "passive"))
      (node (ref "U2") (pin "2") (pinfunction "GND_2") (pintype "passive"))
      (node (ref "U3") (pin "2") (pinfunction "GND_2") (pintype "passive"))
      (node (ref "U4") (pin "10") (pinfunction "XGND_10") (pintype "passive"))
      (node (ref "U4") (pin "62") (pinfunction "GND_62") (pintype "passive"))
      (node (ref "U4") (pin "7") (pinfunction "GND_7") (pintype "passive"))
      (node (ref "U4") (pin "9") (pinfunction "GND_9") (pintype "passive"))
    )
    (net (code "47") (name "Net-(BT1-+)") (class "Default")
      (node (ref "BT1") (pin "1") (pinfunction "+_1") (pintype "passive"))
      (node (ref "D2") (pin "2") (pinfunction "2_2") (pintype "passive"))
    )
    (net (code "48") (name "Net-(C1-Pad2)") (class "Default")
      (node (ref "C1") (pin "2") (pinfunction "2_2") (pintype "passive"))
      (node (ref "KEY1") (pin "1") (pinfunction "1_1") (pintype "passive"))
      (node (ref "R1") (pin "2") (pinfunction "2_2") (pintype "passive"))
    )
    (net (code "49") (name "Net-(C2-Pad2)") (class "Default")
      (node (ref "C2") (pin "2") (pinfunction "2_2") (pintype "passive"))
      (node (ref "KEY4") (pin "1") (pinfunction "1_1") (pintype "passive"))
      (node (ref "R2") (pin "2") (pinfunction "2_2") (pintype "passive"))
    )
    (net (code "50") (name "Net-(C3-Pad2)") (class "Default")
      (node (ref "C3") (pin "2") (pinfunction "2_2") (pintype "passive"))
      (node (ref "KEY7") (pin "1") (pinfunction "1_1") (pintype "passive"))
      (node (ref "R3") (pin "2") (pinfunction "2_2") (pintype "passive"))
    )
    (net (code "51") (name "Net-(C4-Pad2)") (class "Default")
      (node (ref "C4") (pin "2") (pinfunction "2_2") (pintype "passive"))
      (node (ref "KEY10") (pin "1") (pinfunction "1_1") (pintype "passive"))
      (node (ref "R4") (pin "2") (pinfunction "2_2") (pintype "passive"))
    )
    (net (code "52") (name "Net-(C5-Pad2)") (class "Default")
      (node (ref "C5") (pin "2") (pinfunction "2_2") (pintype "passive"))
      (node (ref "KEY2") (pin "1") (pinfunction "1_1") (pintype "passive"))
      (node (ref "R10") (pin "2") (pinfunction "2_2") (pintype "passive"))
    )
    (net (code "53") (name "Net-(C6-Pad2)") (class "Default")
      (node (ref "C6") (pin "2") (pinfunction "2_2") (pintype "passive"))
      (node (ref "KEY3") (pin "1") (pinfunction "1_1") (pintype "passive"))
      (node (ref "R7") (pin "2") (pinfunction "2_2") (pintype "passive"))
    )
    (net (code "54") (name "Net-(C7-Pad2)") (class "Default")
      (node (ref "C7") (pin "2") (pinfunction "2_2") (pintype "passive"))
      (node (ref "KEY5") (pin "1") (pinfunction "1_1") (pintype "passive"))
      (node (ref "R11") (pin "2") (pinfunction "2_2") (pintype "passive"))
    )
    (net (code "55") (name "Net-(C8-Pad2)") (class "Default")
      (node (ref "C8") (pin "2") (pinfunction "2_2") (pintype "passive"))
      (node (ref "KEY6") (pin "1") (pinfunction "1_1") (pintype "passive"))
      (node (ref "R12") (pin "2") (pinfunction "2_2") (pintype "passive"))
    )
    (net (code "56") (name "Net-(C9-Pad2)") (class "Default")
      (node (ref "C9") (pin "2") (pinfunction "2_2") (pintype "passive"))
      (node (ref "KEY8") (pin "1") (pinfunction "1_1") (pintype "passive"))
      (node (ref "R22") (pin "2") (pinfunction "2_2") (pintype "passive"))
    )
    (net (code "57") (name "Net-(C10-Pad2)") (class "Default")
      (node (ref "C10") (pin "2") (pinfunction "2_2") (pintype "passive"))
      (node (ref "KEY9") (pin "1") (pinfunction "1_1") (pintype "passive"))
      (node (ref "R19") (pin "2") (pinfunction "2_2") (pintype "passive"))
    )
    (net (code "58") (name "Net-(C11-Pad2)") (class "Default")
      (node (ref "C11") (pin "2") (pinfunction "2_2") (pintype "passive"))
      (node (ref "KEY11") (pin "1") (pinfunction "1_1") (pintype "passive"))
      (node (ref "R23") (pin "2") (pinfunction "2_2") (pintype "passive"))
    )
    (net (code "59") (name "Net-(C12-Pad2)") (class "Default")
      (node (ref "C12") (pin "2") (pinfunction "2_2") (pintype "passive"))
      (node (ref "KEY12") (pin "1") (pinfunction "1_1") (pintype "passive"))
      (node (ref "R24") (pin "2") (pinfunction "2_2") (pintype "passive"))
    )
    (net (code "60") (name "Net-(D3-AC-Pad1)") (class "Default")
      (node (ref "D3") (pin "1") (pinfunction "AC_1") (pintype "passive"))
      (node (ref "T1") (pin "4") (pinfunction "4_4") (pintype "passive"))
    )
    (net (code "61") (name "Net-(D3-AC-Pad2)") (class "Default")
      (node (ref "D3") (pin "2") (pinfunction "AC_2") (pintype "passive"))
      (node (ref "T1") (pin "6") (pinfunction "6_6") (pintype "passive"))
    )
    (net (code "62") (name "Net-(JP2-N)") (class "Default")
      (node (ref "JP2") (pin "12VIN") (pinfunction "N_12VIN") (pintype "passive"))
      (node (ref "K1") (pin "3") (pinfunction "3_3") (pintype "passive"))
    )
    (net (code "63") (name "Net-(LED1-KB)") (class "Default")
      (node (ref "LED1") (pin "4") (pinfunction "KB_4") (pintype "passive"))
      (node (ref "R44") (pin "2") (pinfunction "2_2") (pintype "passive"))
    )
    (net (code "64") (name "Net-(LED1-KG)") (class "Default")
      (node (ref "LED1") (pin "3") (pinfunction "KG_3") (pintype "passive"))
      (node (ref "R45") (pin "2") (pinfunction "2_2") (pintype "passive"))
    )
    (net (code "65") (name "Net-(LED1-KR)") (class "Default")
      (node (ref "LED1") (pin "1") (pinfunction "KR_1") (pintype "passive"))
      (node (ref "R46") (pin "2") (pinfunction "2_2") (pintype "passive"))
    )
    (net (code "66") (name "Net-(Q1-B)") (class "Default")
      (node (ref "Q1") (pin "1") (pinfunction "B_1") (pintype "passive"))
      (node (ref "R25") (pin "2") (pinfunction "2_2") (pintype "passive"))
    )
    (net (code "67") (name "Net-(Q2-B)") (class "Default")
      (node (ref "Q2") (pin "1") (pinfunction "B_1") (pintype "passive"))
      (node (ref "R26") (pin "2") (pinfunction "2_2") (pintype "passive"))
    )
    (net (code "68") (name "Net-(Q3-B)") (class "Default")
      (node (ref "Q3") (pin "1") (pinfunction "B_1") (pintype "passive"))
      (node (ref "R27") (pin "2") (pinfunction "2_2") (pintype "passive"))
    )
    (net (code "69") (name "Net-(Q4-B)") (class "Default")
      (node (ref "Q4") (pin "1") (pinfunction "B_1") (pintype "passive"))
      (node (ref "R28") (pin "2") (pinfunction "2_2") (pintype "passive"))
    )
    (net (code "70") (name "Net-(Q5-B)") (class "Default")
      (node (ref "Q5") (pin "1") (pinfunction "B_1") (pintype "passive"))
      (node (ref "R29") (pin "2") (pinfunction "2_2") (pintype "passive"))
    )
    (net (code "71") (name "Net-(Q6-B)") (class "Default")
      (node (ref "Q6") (pin "1") (pinfunction "B_1") (pintype "passive"))
      (node (ref "R30") (pin "2") (pinfunction "2_2") (pintype "passive"))
    )
    (net (code "72") (name "Net-(Q7-B)") (class "Default")
      (node (ref "Q7") (pin "1") (pinfunction "B_1") (pintype "passive"))
      (node (ref "R31") (pin "2") (pinfunction "2_2") (pintype "passive"))
    )
    (net (code "73") (name "Net-(Q8-B)") (class "Default")
      (node (ref "Q8") (pin "1") (pinfunction "B_1") (pintype "passive"))
      (node (ref "R32") (pin "2") (pinfunction "2_2") (pintype "passive"))
    )
    (net (code "74") (name "Net-(Q9-B)") (class "Default")
      (node (ref "Q9") (pin "1") (pinfunction "B_1") (pintype "passive"))
      (node (ref "R55") (pin "2") (pinfunction "2_2") (pintype "passive"))
    )
    (net (code "75") (name "Net-(Q10-B)") (class "Default")
      (node (ref "Q10") (pin "1") (pinfunction "B_1") (pintype "passive"))
      (node (ref "R56") (pin "2") (pinfunction "2_2") (pintype "passive"))
    )
    (net (code "76") (name "Net-(Q10-E)") (class "Default")
      (node (ref "Q10") (pin "2") (pinfunction "E_2") (pintype "passive"))
      (node (ref "Q11") (pin "2") (pinfunction "E_2") (pintype "passive"))
      (node (ref "Q9") (pin "2") (pinfunction "E_2") (pintype "passive"))
    )
    (net (code "77") (name "Net-(Q11-B)") (class "Default")
      (node (ref "Q11") (pin "1") (pinfunction "B_1") (pintype "passive"))
      (node (ref "R57") (pin "2") (pinfunction "2_2") (pintype "passive"))
    )
    (net (code "78") (name "Net-(Q12-B)") (class "Default")
      (node (ref "Q12") (pin "1") (pinfunction "B_1") (pintype "passive"))
      (node (ref "R58") (pin "2") (pinfunction "2_2") (pintype "passive"))
    )
    (net (code "79") (name "Net-(Q12-C)") (class "Default")
      (node (ref "D1") (pin "2") (pinfunction "2_2") (pintype "passive"))
      (node (ref "K1") (pin "2") (pinfunction "2_2") (pintype "passive"))
      (node (ref "Q12") (pin "3") (pinfunction "C_3") (pintype "passive"))
    )
    (net (code "80") (name "Net-(Q13-B)") (class "Default")
      (node (ref "Q13") (pin "1") (pinfunction "B_1") (pintype "passive"))
      (node (ref "R60") (pin "2") (pinfunction "2_2") (pintype "passive"))
    )
    (net (code "81") (name "Net-(Q13-C)") (class "Default")
      (node (ref "BUZZER1") (pin "1") (pinfunction "1_1") (pintype "passive"))
      (node (ref "Q13") (pin "3") (pinfunction "C_3") (pintype "passive"))
      (node (ref "R59") (pin "1") (pinfunction "1_1") (pintype "passive"))
    )
    (net (code "82") (name "Net-(SEG1-A)") (class "Default")
      (node (ref "R47") (pin "2") (pinfunction "2_2") (pintype "passive"))
      (node (ref "SEG1") (pin "11") (pinfunction "A_11") (pintype "passive"))
    )
    (net (code "83") (name "Net-(SEG1-B)") (class "Default")
      (node (ref "R48") (pin "2") (pinfunction "2_2") (pintype "passive"))
      (node (ref "SEG1") (pin "7") (pinfunction "B_7") (pintype "passive"))
    )
    (net (code "84") (name "Net-(SEG1-C)") (class "Default")
      (node (ref "R49") (pin "2") (pinfunction "2_2") (pintype "passive"))
      (node (ref "SEG1") (pin "4") (pinfunction "C_4") (pintype "passive"))
    )
    (net (code "85") (name "Net-(SEG1-D)") (class "Default")
      (node (ref "R50") (pin "2") (pinfunction "2_2") (pintype "passive"))
      (node (ref "SEG1") (pin "2") (pinfunction "D_2") (pintype "passive"))
    )
    (net (code "86") (name "Net-(SEG1-DP)") (class "Default")
      (node (ref "R54") (pin "2") (pinfunction "2_2") (pintype "passive"))
      (node (ref "SEG1") (pin "3") (pinfunction "DP_3") (pintype "passive"))
    )
    (net (code "87") (name "Net-(SEG1-E)") (class "Default")
      (node (ref "R51") (pin "2") (pinfunction "2_2") (pintype "passive"))
      (node (ref "SEG1") (pin "1") (pinfunction "E_1") (pintype "passive"))
    )
    (net (code "88") (name "Net-(SEG1-F)") (class "Default")
      (node (ref "R52") (pin "2") (pinfunction "2_2") (pintype "passive"))
      (node (ref "SEG1") (pin "10") (pinfunction "F_10") (pintype "passive"))
    )
    (net (code "89") (name "Net-(SEG1-G)") (class "Default")
      (node (ref "R53") (pin "2") (pinfunction "2_2") (pintype "passive"))
      (node (ref "SEG1") (pin "5") (pinfunction "G_5") (pintype "passive"))
    )
    (net (code "90") (name "VCC") (class "Default")
      (node (ref "D3") (pin "3") (pinfunction "+_3") (pintype "passive"))
      (node (ref "U1") (pin "3") (pinfunction "VIN_3") (pintype "passive"))
      (node (ref "U2") (pin "1") (pinfunction "IN_1") (pintype "passive"))
      (node (ref "U3") (pin "1") (pinfunction "IN_1") (pintype "passive"))
    )
    (net (code "91") (name "unconnected-(T1-Pad2)") (class "Default")
      (node (ref "T1") (pin "2") (pinfunction "2_2") (pintype "passive+no_connect"))
    )
    (net (code "92") (name "unconnected-(T1-Pad5)") (class "Default")
      (node (ref "T1") (pin "5") (pinfunction "5_5") (pintype "passive+no_connect"))
    )
    (net (code "93") (name "unconnected-(U4-A0-Pad13)") (class "Default")
      (node (ref "U4") (pin "13") (pinfunction "A0_13") (pintype "passive+no_connect"))
    )
    (net (code "94") (name "unconnected-(U4-A1-Pad15)") (class "Default")
      (node (ref "U4") (pin "15") (pinfunction "A1_15") (pintype "passive+no_connect"))
    )
    (net (code "95") (name "unconnected-(U4-A2-Pad17)") (class "Default")
      (node (ref "U4") (pin "17") (pinfunction "A2_17") (pintype "passive+no_connect"))
    )
    (net (code "96") (name "unconnected-(U4-A3-Pad19)") (class "Default")
      (node (ref "U4") (pin "19") (pinfunction "A3_19") (pintype "passive+no_connect"))
    )
    (net (code "97") (name "unconnected-(U4-A4-Pad21)") (class "Default")
      (node (ref "U4") (pin "21") (pinfunction "A4_21") (pintype "passive+no_connect"))
    )
    (net (code "98") (name "unconnected-(U4-A5-Pad23)") (class "Default")
      (node (ref "U4") (pin "23") (pinfunction "A5_23") (pintype "passive+no_connect"))
    )
    (net (code "99") (name "unconnected-(U4-A6-Pad14)") (class "Default")
      (node (ref "U4") (pin "14") (pinfunction "A6_14") (pintype "passive+no_connect"))
    )
    (net (code "100") (name "unconnected-(U4-A7-Pad16)") (class "Default")
      (node (ref "U4") (pin "16") (pinfunction "A7_16") (pintype "passive+no_connect"))
    )
    (net (code "101") (name "unconnected-(U4-A8-Pad18)") (class "Default")
      (node (ref "U4") (pin "18") (pinfunction "A8_18") (pintype "passive+no_connect"))
    )
    (net (code "102") (name "unconnected-(U4-A9-Pad20)") (class "Default")
      (node (ref "U4") (pin "20") (pinfunction "A9_20") (pintype "passive+no_connect"))
    )
    (net (code "103") (name "unconnected-(U4-A10-Pad22)") (class "Default")
      (node (ref "U4") (pin "22") (pinfunction "A10_22") (pintype "passive+no_connect"))
    )
    (net (code "104") (name "unconnected-(U4-A11-Pad24)") (class "Default")
      (node (ref "U4") (pin "24") (pinfunction "A11_24") (pintype "passive+no_connect"))
    )
    (net (code "105") (name "unconnected-(U4-A_(IO42)-Pad28)") (class "Default")
      (node (ref "U4") (pin "28") (pinfunction "A_(IO42)_28") (pintype "passive+no_connect"))
    )
    (net (code "106") (name "unconnected-(U4-G-Pad30)") (class "Default")
      (node (ref "U4") (pin "30") (pinfunction "G_30") (pintype "passive+no_connect"))
    )
    (net (code "107") (name "unconnected-(U4-IO39-Pad31)") (class "Default")
      (node (ref "U4") (pin "31") (pinfunction "IO39_31") (pintype "passive+no_connect"))
    )
    (net (code "108") (name "unconnected-(U4-IOREF-Pad2)") (class "Default")
      (node (ref "U4") (pin "2") (pinfunction "IOREF_2") (pintype "passive+no_connect"))
    )
    (net (code "109") (name "unconnected-(U4-MISO-Pad61)") (class "Default")
      (node (ref "U4") (pin "61") (pinfunction "MISO_61") (pintype "passive+no_connect"))
    )
    (net (code "110") (name "unconnected-(U4-MOSI-Pad63)") (class "Default")
      (node (ref "U4") (pin "63") (pinfunction "MOSI_63") (pintype "passive+no_connect"))
    )
    (net (code "111") (name "unconnected-(U4-N{slash}C-Pad1)") (class "Default")
      (node (ref "U4") (pin "1") (pinfunction "N/C_1") (pintype "passive+no_connect"))
    )
    (net (code "112") (name "unconnected-(U4-N{slash}C-Pad64)") (class "Default")
      (node (ref "U4") (pin "64") (pinfunction "N/C_64") (pintype "passive+no_connect"))
    )
    (net (code "113") (name "unconnected-(U4-RST-Pad3)") (class "Default")
      (node (ref "U4") (pin "3") (pinfunction "RST_3") (pintype "passive+no_connect"))
    )
    (net (code "114") (name "unconnected-(U4-SCL-Pad25)") (class "Default")
      (node (ref "U4") (pin "25") (pinfunction "SCL_25") (pintype "passive+no_connect"))
    )
    (net (code "115") (name "unconnected-(U4-SCLK-Pad60)") (class "Default")
      (node (ref "U4") (pin "60") (pinfunction "SCLK_60") (pintype "passive+no_connect"))
    )
    (net (code "116") (name "unconnected-(U4-SDA-Pad26)") (class "Default")
      (node (ref "U4") (pin "26") (pinfunction "SDA_26") (pintype "passive+no_connect"))
    )
    (net (code "117") (name "unconnected-(U4-SS-Pad59)") (class "Default")
      (node (ref "U4") (pin "59") (pinfunction "SS_59") (pintype "passive+no_connect"))
    )
    (net (code "118") (name "unconnected-(U4-VIN-Pad11)") (class "Default")
      (node (ref "U4") (pin "11") (pinfunction "VIN_11") (pintype "passive+no_connect"))
    )
    (net (code "119") (name "unconnected-(U4-V_N-Pad8)") (class "Default")
      (node (ref "U4") (pin "8") (pinfunction "V_N_8") (pintype "passive+no_connect"))
    )
    (net (code "120") (name "unconnected-(U4-V_P-Pad6)") (class "Default")
      (node (ref "U4") (pin "6") (pinfunction "V_P_6") (pintype "passive+no_connect"))
    )
    (net (code "121") (name "unconnected-(U4-XVREF-Pad12)") (class "Default")
      (node (ref "U4") (pin "12") (pinfunction "XVREF_12") (pintype "passive+no_connect"))
    )
  )
)
